# 3_IO_Module.net
KiCad netlist of a schematic drawn in Altium Designer
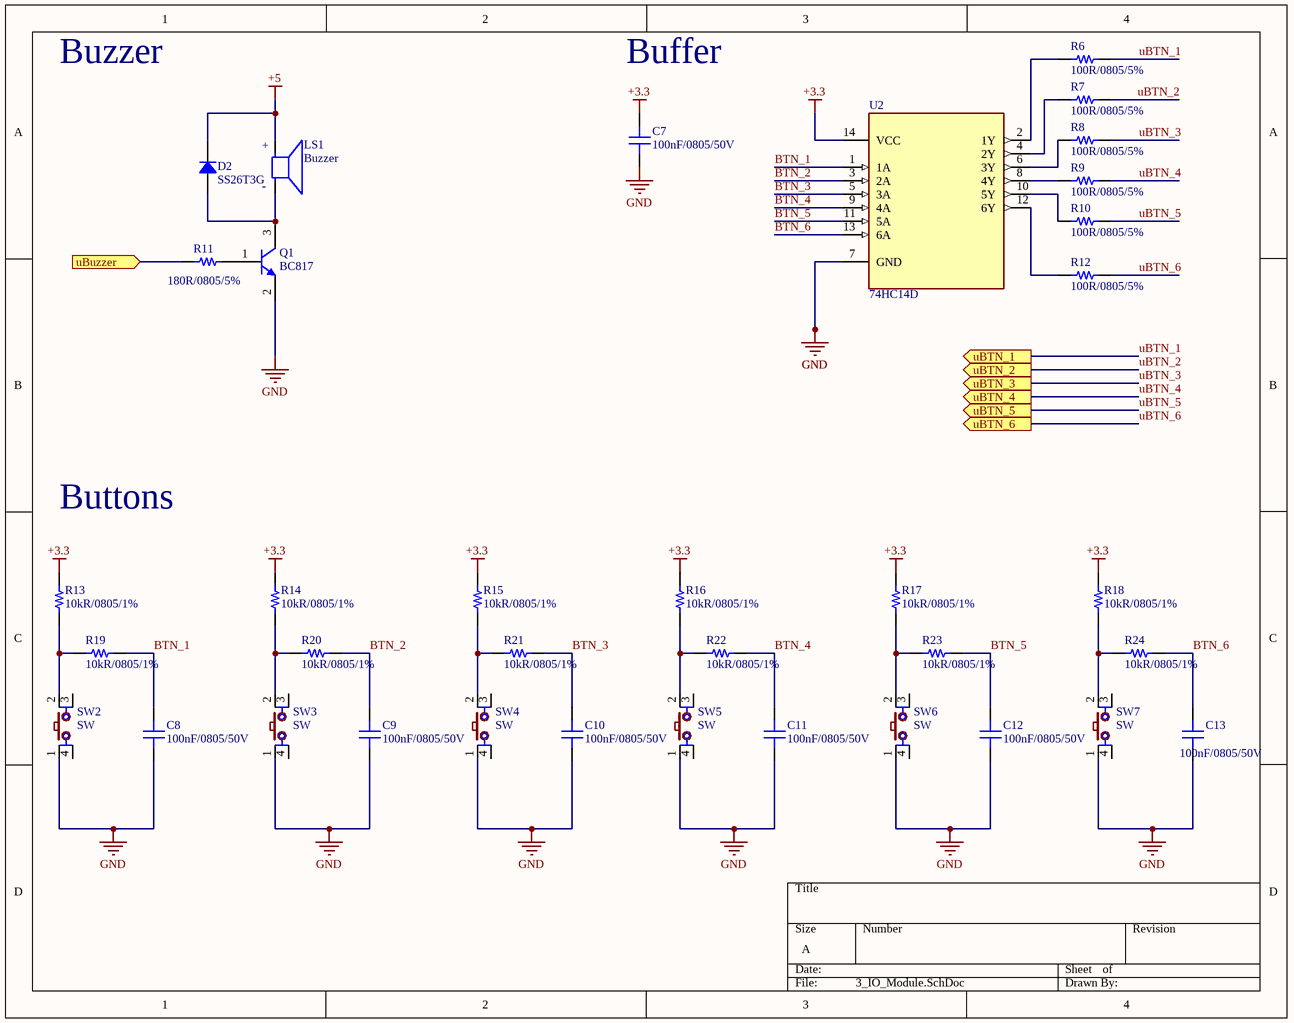
[diagram p0: 3_IO_Module.SchDoc]

(export (version "E")
  (design (tool "Eeschema 10.0.6"))
  (components
    (comp (ref "C7")
      (value "100nF/0805/50V")
      (footprint "CAP FILM 0805")
      (description "Multilayer Ceramic Capacitor, 0.1 uF, 50 V, ï¿½ 10%, X7R, 0805 [2012 Metric]")
      (fields
        (field (name "MANUFACTURER") "Samsung")
        (field (name "MANUFACTURER PART NUMBER") "CL21B104KBCNNNC")
      )
      (libsource (lib "NLOC_Altium_Library") (part "Capacitor - MLCC"))
    )
    (comp (ref "C8")
      (value "100nF/0805/50V")
      (footprint "CAP FILM 0805")
      (description "Multilayer Ceramic Capacitor, 0.1 uF, 50 V, ï¿½ 10%, X7R, 0805 [2012 Metric]")
      (fields
        (field (name "MANUFACTURER") "Samsung")
        (field (name "MANUFACTURER PART NUMBER") "CL21B104KBCNNNC")
      )
      (libsource (lib "NLOC_Altium_Library") (part "Capacitor - MLCC"))
    )
    (comp (ref "C9")
      (value "100nF/0805/50V")
      (footprint "CAP FILM 0805")
      (description "Multilayer Ceramic Capacitor, 0.1 uF, 50 V, ï¿½ 10%, X7R, 0805 [2012 Metric]")
      (fields
        (field (name "MANUFACTURER") "Samsung")
        (field (name "MANUFACTURER PART NUMBER") "CL21B104KBCNNNC")
      )
      (libsource (lib "NLOC_Altium_Library") (part "Capacitor - MLCC"))
    )
    (comp (ref "C10")
      (value "100nF/0805/50V")
      (footprint "CAP FILM 0805")
      (description "Multilayer Ceramic Capacitor, 0.1 uF, 50 V, ï¿½ 10%, X7R, 0805 [2012 Metric]")
      (fields
        (field (name "MANUFACTURER") "Samsung")
        (field (name "MANUFACTURER PART NUMBER") "CL21B104KBCNNNC")
      )
      (libsource (lib "NLOC_Altium_Library") (part "Capacitor - MLCC"))
    )
    (comp (ref "C11")
      (value "100nF/0805/50V")
      (footprint "CAP FILM 0805")
      (description "Multilayer Ceramic Capacitor, 0.1 uF, 50 V, ï¿½ 10%, X7R, 0805 [2012 Metric]")
      (fields
        (field (name "MANUFACTURER") "Samsung")
        (field (name "MANUFACTURER PART NUMBER") "CL21B104KBCNNNC")
      )
      (libsource (lib "NLOC_Altium_Library") (part "Capacitor - MLCC"))
    )
    (comp (ref "C12")
      (value "100nF/0805/50V")
      (footprint "CAP FILM 0805")
      (description "Multilayer Ceramic Capacitor, 0.1 uF, 50 V, ï¿½ 10%, X7R, 0805 [2012 Metric]")
      (fields
        (field (name "MANUFACTURER") "Samsung")
        (field (name "MANUFACTURER PART NUMBER") "CL21B104KBCNNNC")
      )
      (libsource (lib "NLOC_Altium_Library") (part "Capacitor - MLCC"))
    )
    (comp (ref "C13")
      (value "100nF/0805/50V")
      (footprint "CAP FILM 0805")
      (description "Multilayer Ceramic Capacitor, 0.1 uF, 50 V, ï¿½ 10%, X7R, 0805 [2012 Metric]")
      (fields
        (field (name "MANUFACTURER") "Samsung")
        (field (name "MANUFACTURER PART NUMBER") "CL21B104KBCNNNC")
      )
      (libsource (lib "NLOC_Altium_Library") (part "Capacitor - MLCC"))
    )
    (comp (ref "D2")
      (value "SS26T3G")
      (footprint "ST DO214AC SMA")
      (description "VR=60V IF=2A")
      (fields (field (name "MANUFACTURER") "ON Semiconductor"))
      (libsource (lib "NLOC_Altium_Library") (part "Diode"))
    )
    (comp (ref "LS1")
      (value "Buzzer")
      (footprint "XDCR_AT-1224-TWT-5V-2-R")
      (description "AUDIO TRANSDUCER 12 VP-P 85 DB 2400 HZ")
      (fields (field (name "MP") "AT-1224-TWT-5V-2-R"))
      (libsource (lib "AT-1224-TWT-5V-2-R") (part "AT-1224-TWT-5V-2-R"))
    )
    (comp (ref "Q1")
      (value "BC817")
      (footprint "TI SOT-23-3 DBZ")
      (libsource (lib "NLOC_Altium_Library") (part "BJT NPN"))
    )
    (comp (ref "R6")
      (value "100R/0805/5%")
      (footprint "RES 0805_2012")
      (description "SMD Chip Resistor, 100 Ohm, ± 5%, 125 mW, 0805 [2012 Metric], Thick Film, General Purpose")
      (fields
        (field (name "MANUFACTURER") "Yageo")
        (field (name "MANUFACTURER PART NUMBER") "AC0805JR-07100RL")
      )
      (libsource (lib "NLOC_Altium_Library") (part "Resistor"))
    )
    (comp (ref "R7")
      (value "100R/0805/5%")
      (footprint "RES 0805_2012")
      (description "SMD Chip Resistor, 100 Ohm, ± 5%, 125 mW, 0805 [2012 Metric], Thick Film, General Purpose")
      (fields
        (field (name "MANUFACTURER") "Yageo")
        (field (name "MANUFACTURER PART NUMBER") "AC0805JR-07100RL")
      )
      (libsource (lib "NLOC_Altium_Library") (part "Resistor"))
    )
    (comp (ref "R8")
      (value "100R/0805/5%")
      (footprint "RES 0805_2012")
      (description "SMD Chip Resistor, 100 Ohm, ± 5%, 125 mW, 0805 [2012 Metric], Thick Film, General Purpose")
      (fields
        (field (name "MANUFACTURER") "Yageo")
        (field (name "MANUFACTURER PART NUMBER") "AC0805JR-07100RL")
      )
      (libsource (lib "NLOC_Altium_Library") (part "Resistor"))
    )
    (comp (ref "R9")
      (value "100R/0805/5%")
      (footprint "RES 0805_2012")
      (description "SMD Chip Resistor, 100 Ohm, ± 5%, 125 mW, 0805 [2012 Metric], Thick Film, General Purpose")
      (fields
        (field (name "MANUFACTURER") "Yageo")
        (field (name "MANUFACTURER PART NUMBER") "AC0805JR-07100RL")
      )
      (libsource (lib "NLOC_Altium_Library") (part "Resistor"))
    )
    (comp (ref "R10")
      (value "100R/0805/5%")
      (footprint "RES 0805_2012")
      (description "SMD Chip Resistor, 100 Ohm, ± 5%, 125 mW, 0805 [2012 Metric], Thick Film, General Purpose")
      (fields
        (field (name "MANUFACTURER") "Yageo")
        (field (name "MANUFACTURER PART NUMBER") "AC0805JR-07100RL")
      )
      (libsource (lib "NLOC_Altium_Library") (part "Resistor"))
    )
    (comp (ref "R11")
      (value "180R/0805/5%")
      (footprint "RES 0805_2012")
      (description "Anti-Sulfurated Chip Resistor Thick Film 0805 180Ohm 1% Paper T/R")
      (fields
        (field (name "MANUFACTURER") "Yageo")
        (field (name "MANUFACTURER PART NUMBER") "AF0805FR-07180RL")
      )
      (libsource (lib "NLOC_Altium_Library") (part "Resistor"))
    )
    (comp (ref "R12")
      (value "100R/0805/5%")
      (footprint "RES 0805_2012")
      (description "SMD Chip Resistor, 100 Ohm, ± 5%, 125 mW, 0805 [2012 Metric], Thick Film, General Purpose")
      (fields
        (field (name "MANUFACTURER") "Yageo")
        (field (name "MANUFACTURER PART NUMBER") "AC0805JR-07100RL")
      )
      (libsource (lib "NLOC_Altium_Library") (part "Resistor"))
    )
    (comp (ref "R13")
      (value "10kR/0805/1%")
      (footprint "RES 0805_2012")
      (description "SMD Chip Resistor, 10 kOhm, ï¿½ 1%, 125 mW, 0805 [2012 Metric], Thick Film, General Purpose")
      (fields
        (field (name "MANUFACTURER") "Yageo")
        (field (name "MANUFACTURER PART NUMBER") "RC0805FR-0710KL")
      )
      (libsource (lib "NLOC_Altium_Library") (part "Resistor"))
    )
    (comp (ref "R14")
      (value "10kR/0805/1%")
      (footprint "RES 0805_2012")
      (description "SMD Chip Resistor, 10 kOhm, ï¿½ 1%, 125 mW, 0805 [2012 Metric], Thick Film, General Purpose")
      (fields
        (field (name "MANUFACTURER") "Yageo")
        (field (name "MANUFACTURER PART NUMBER") "RC0805FR-0710KL")
      )
      (libsource (lib "NLOC_Altium_Library") (part "Resistor"))
    )
    (comp (ref "R15")
      (value "10kR/0805/1%")
      (footprint "RES 0805_2012")
      (description "SMD Chip Resistor, 10 kOhm, ï¿½ 1%, 125 mW, 0805 [2012 Metric], Thick Film, General Purpose")
      (fields
        (field (name "MANUFACTURER") "Yageo")
        (field (name "MANUFACTURER PART NUMBER") "RC0805FR-0710KL")
      )
      (libsource (lib "NLOC_Altium_Library") (part "Resistor"))
    )
    (comp (ref "R16")
      (value "10kR/0805/1%")
      (footprint "RES 0805_2012")
      (description "SMD Chip Resistor, 10 kOhm, ï¿½ 1%, 125 mW, 0805 [2012 Metric], Thick Film, General Purpose")
      (fields
        (field (name "MANUFACTURER") "Yageo")
        (field (name "MANUFACTURER PART NUMBER") "RC0805FR-0710KL")
      )
      (libsource (lib "NLOC_Altium_Library") (part "Resistor"))
    )
    (comp (ref "R17")
      (value "10kR/0805/1%")
      (footprint "RES 0805_2012")
      (description "SMD Chip Resistor, 10 kOhm, ï¿½ 1%, 125 mW, 0805 [2012 Metric], Thick Film, General Purpose")
      (fields
        (field (name "MANUFACTURER") "Yageo")
        (field (name "MANUFACTURER PART NUMBER") "RC0805FR-0710KL")
      )
      (libsource (lib "NLOC_Altium_Library") (part "Resistor"))
    )
    (comp (ref "R18")
      (value "10kR/0805/1%")
      (footprint "RES 0805_2012")
      (description "SMD Chip Resistor, 10 kOhm, ï¿½ 1%, 125 mW, 0805 [2012 Metric], Thick Film, General Purpose")
      (fields
        (field (name "MANUFACTURER") "Yageo")
        (field (name "MANUFACTURER PART NUMBER") "RC0805FR-0710KL")
      )
      (libsource (lib "NLOC_Altium_Library") (part "Resistor"))
    )
    (comp (ref "R19")
      (value "10kR/0805/1%")
      (footprint "RES 0805_2012")
      (description "SMD Chip Resistor, 10 kOhm, ï¿½ 1%, 125 mW, 0805 [2012 Metric], Thick Film, General Purpose")
      (fields
        (field (name "MANUFACTURER") "Yageo")
        (field (name "MANUFACTURER PART NUMBER") "RC0805FR-0710KL")
      )
      (libsource (lib "NLOC_Altium_Library") (part "Resistor"))
    )
    (comp (ref "R20")
      (value "10kR/0805/1%")
      (footprint "RES 0805_2012")
      (description "SMD Chip Resistor, 10 kOhm, ï¿½ 1%, 125 mW, 0805 [2012 Metric], Thick Film, General Purpose")
      (fields
        (field (name "MANUFACTURER") "Yageo")
        (field (name "MANUFACTURER PART NUMBER") "RC0805FR-0710KL")
      )
      (libsource (lib "NLOC_Altium_Library") (part "Resistor"))
    )
    (comp (ref "R21")
      (value "10kR/0805/1%")
      (footprint "RES 0805_2012")
      (description "SMD Chip Resistor, 10 kOhm, ï¿½ 1%, 125 mW, 0805 [2012 Metric], Thick Film, General Purpose")
      (fields
        (field (name "MANUFACTURER") "Yageo")
        (field (name "MANUFACTURER PART NUMBER") "RC0805FR-0710KL")
      )
      (libsource (lib "NLOC_Altium_Library") (part "Resistor"))
    )
    (comp (ref "R22")
      (value "10kR/0805/1%")
      (footprint "RES 0805_2012")
      (description "SMD Chip Resistor, 10 kOhm, ï¿½ 1%, 125 mW, 0805 [2012 Metric], Thick Film, General Purpose")
      (fields
        (field (name "MANUFACTURER") "Yageo")
        (field (name "MANUFACTURER PART NUMBER") "RC0805FR-0710KL")
      )
      (libsource (lib "NLOC_Altium_Library") (part "Resistor"))
    )
    (comp (ref "R23")
      (value "10kR/0805/1%")
      (footprint "RES 0805_2012")
      (description "SMD Chip Resistor, 10 kOhm, ï¿½ 1%, 125 mW, 0805 [2012 Metric], Thick Film, General Purpose")
      (fields
        (field (name "MANUFACTURER") "Yageo")
        (field (name "MANUFACTURER PART NUMBER") "RC0805FR-0710KL")
      )
      (libsource (lib "NLOC_Altium_Library") (part "Resistor"))
    )
    (comp (ref "R24")
      (value "10kR/0805/1%")
      (footprint "RES 0805_2012")
      (description "SMD Chip Resistor, 10 kOhm, ï¿½ 1%, 125 mW, 0805 [2012 Metric], Thick Film, General Purpose")
      (fields
        (field (name "MANUFACTURER") "Yageo")
        (field (name "MANUFACTURER PART NUMBER") "RC0805FR-0710KL")
      )
      (libsource (lib "NLOC_Altium_Library") (part "Resistor"))
    )
    (comp (ref "SW2")
      (value "SW")
      (footprint "SW2-SMD")
      (description "Switch button 4 pin")
      (libsource (lib "LIBRARYALT") (part "SW4"))
    )
    (comp (ref "SW3")
      (value "SW")
      (footprint "SW2-SMD")
      (description "Switch button 4 pin")
      (libsource (lib "LIBRARYALT") (part "SW4"))
    )
    (comp (ref "SW4")
      (value "SW")
      (footprint "SW2-SMD")
      (description "Switch button 4 pin")
      (libsource (lib "LIBRARYALT") (part "SW4"))
    )
    (comp (ref "SW5")
      (value "SW")
      (footprint "SW2-SMD")
      (description "Switch button 4 pin")
      (libsource (lib "LIBRARYALT") (part "SW4"))
    )
    (comp (ref "SW6")
      (value "SW")
      (footprint "SW2-SMD")
      (description "Switch button 4 pin")
      (libsource (lib "LIBRARYALT") (part "SW4"))
    )
    (comp (ref "SW7")
      (value "SW")
      (footprint "SW2-SMD")
      (description "Switch button 4 pin")
      (libsource (lib "LIBRARYALT") (part "SW4"))
    )
    (comp (ref "U2")
      (value "74HC14D")
      (footprint "SOIC127P600X175-14N")
      (description "Inverter IC 6 Channel Schmitt Trigger 14-SOIC")
      (fields (field (name "MF") "Toshiba"))
      (libsource (lib "74HC14D") (part "74HC14D"))
    )
  )
  (nets
    (net (code "1") (name "+3.3") (class "Default")
      (node (ref "C7") (pin "2") (pinfunction "2_2") (pintype "passive"))
      (node (ref "R13") (pin "2") (pinfunction "2_2") (pintype "passive"))
      (node (ref "R14") (pin "2") (pinfunction "2_2") (pintype "passive"))
      (node (ref "R15") (pin "2") (pinfunction "2_2") (pintype "passive"))
      (node (ref "R16") (pin "2") (pinfunction "2_2") (pintype "passive"))
      (node (ref "R17") (pin "2") (pinfunction "2_2") (pintype "passive"))
      (node (ref "R18") (pin "2") (pinfunction "2_2") (pintype "passive"))
      (node (ref "U2") (pin "14") (pinfunction "VCC_14") (pintype "power_in"))
    )
    (net (code "2") (name "+5") (class "Default")
      (node (ref "D2") (pin "2") (pinfunction "2_2") (pintype "passive"))
      (node (ref "LS1") (pin "P") (pinfunction "P_P") (pintype "passive"))
    )
    (net (code "3") (name "/BTN_1") (class "Default")
      (node (ref "C8") (pin "2") (pinfunction "2_2") (pintype "passive"))
      (node (ref "R19") (pin "1") (pinfunction "1_1") (pintype "passive"))
      (node (ref "U2") (pin "1") (pinfunction "1A_1") (pintype "input"))
    )
    (net (code "4") (name "/BTN_2") (class "Default")
      (node (ref "C9") (pin "2") (pinfunction "2_2") (pintype "passive"))
      (node (ref "R20") (pin "1") (pinfunction "1_1") (pintype "passive"))
      (node (ref "U2") (pin "3") (pinfunction "2A_3") (pintype "input"))
    )
    (net (code "5") (name "/BTN_3") (class "Default")
      (node (ref "C10") (pin "2") (pinfunction "2_2") (pintype "passive"))
      (node (ref "R21") (pin "1") (pinfunction "1_1") (pintype "passive"))
      (node (ref "U2") (pin "5") (pinfunction "3A_5") (pintype "input"))
    )
    (net (code "6") (name "/BTN_4") (class "Default")
      (node (ref "C11") (pin "2") (pinfunction "2_2") (pintype "passive"))
      (node (ref "R22") (pin "1") (pinfunction "1_1") (pintype "passive"))
      (node (ref "U2") (pin "9") (pinfunction "4A_9") (pintype "input"))
    )
    (net (code "7") (name "/BTN_5") (class "Default")
      (node (ref "C12") (pin "2") (pinfunction "2_2") (pintype "passive"))
      (node (ref "R23") (pin "1") (pinfunction "1_1") (pintype "passive"))
      (node (ref "U2") (pin "11") (pinfunction "5A_11") (pintype "input"))
    )
    (net (code "8") (name "/BTN_6") (class "Default")
      (node (ref "C13") (pin "2") (pinfunction "2_2") (pintype "passive"))
      (node (ref "R24") (pin "1") (pinfunction "1_1") (pintype "passive"))
      (node (ref "U2") (pin "13") (pinfunction "6A_13") (pintype "input"))
    )
    (net (code "9") (name "/uBTN_1") (class "Default")
      (node (ref "R6") (pin "2") (pinfunction "2_2") (pintype "passive"))
    )
    (net (code "10") (name "/uBTN_2") (class "Default")
      (node (ref "R7") (pin "2") (pinfunction "2_2") (pintype "passive"))
    )
    (net (code "11") (name "/uBTN_3") (class "Default")
      (node (ref "R8") (pin "2") (pinfunction "2_2") (pintype "passive"))
    )
    (net (code "12") (name "/uBTN_4") (class "Default")
      (node (ref "R9") (pin "2") (pinfunction "2_2") (pintype "passive"))
    )
    (net (code "13") (name "/uBTN_5") (class "Default")
      (node (ref "R10") (pin "2") (pinfunction "2_2") (pintype "passive"))
    )
    (net (code "14") (name "/uBTN_6") (class "Default")
      (node (ref "R12") (pin "2") (pinfunction "2_2") (pintype "passive"))
    )
    (net (code "15") (name "/uBuzzer") (class "Default")
      (node (ref "R11") (pin "2") (pinfunction "2_2") (pintype "passive"))
    )
    (net (code "16") (name "GND") (class "Default")
      (node (ref "C10") (pin "1") (pinfunction "1_1") (pintype "passive"))
      (node (ref "C11") (pin "1") (pinfunction "1_1") (pintype "passive"))
      (node (ref "C12") (pin "1") (pinfunction "1_1") (pintype "passive"))
      (node (ref "C13") (pin "1") (pinfunction "1_1") (pintype "passive"))
      (node (ref "C7") (pin "1") (pinfunction "1_1") (pintype "passive"))
      (node (ref "C8") (pin "1") (pinfunction "1_1") (pintype "passive"))
      (node (ref "C9") (pin "1") (pinfunction "1_1") (pintype "passive"))
      (node (ref "Q1") (pin "2") (pinfunction "E_2") (pintype "passive"))
      (node (ref "SW2") (pin "1") (pintype "passive"))
      (node (ref "SW3") (pin "1") (pintype "passive"))
      (node (ref "SW4") (pin "1") (pintype "passive"))
      (node (ref "SW5") (pin "1") (pintype "passive"))
      (node (ref "SW6") (pin "1") (pintype "passive"))
      (node (ref "SW7") (pin "1") (pintype "passive"))
      (node (ref "U2") (pin "7") (pinfunction "GND_7") (pintype "passive"))
    )
    (net (code "17") (name "Net-(Q1-B)") (class "Default")
      (node (ref "Q1") (pin "1") (pinfunction "B_1") (pintype "passive"))
      (node (ref "R11") (pin "1") (pinfunction "1_1") (pintype "passive"))
    )
    (net (code "18") (name "Net-(Q1-C)") (class "Default")
      (node (ref "D2") (pin "1") (pinfunction "1_1") (pintype "passive"))
      (node (ref "LS1") (pin "N") (pinfunction "N_N") (pintype "passive"))
      (node (ref "Q1") (pin "3") (pinfunction "C_3") (pintype "passive"))
    )
    (net (code "19") (name "Net-(R13-Pad1)") (class "Default")
      (node (ref "R13") (pin "1") (pinfunction "1_1") (pintype "passive"))
      (node (ref "R19") (pin "2") (pinfunction "2_2") (pintype "passive"))
      (node (ref "SW2") (pin "2") (pinfunction "2_2") (pintype "passive"))
    )
    (net (code "20") (name "Net-(R14-Pad1)") (class "Default")
      (node (ref "R14") (pin "1") (pinfunction "1_1") (pintype "passive"))
      (node (ref "R20") (pin "2") (pinfunction "2_2") (pintype "passive"))
      (node (ref "SW3") (pin "2") (pinfunction "2_2") (pintype "passive"))
    )
    (net (code "21") (name "Net-(R15-Pad1)") (class "Default")
      (node (ref "R15") (pin "1") (pinfunction "1_1") (pintype "passive"))
      (node (ref "R21") (pin "2") (pinfunction "2_2") (pintype "passive"))
      (node (ref "SW4") (pin "2") (pinfunction "2_2") (pintype "passive"))
    )
    (net (code "22") (name "Net-(R16-Pad1)") (class "Default")
      (node (ref "R16") (pin "1") (pinfunction "1_1") (pintype "passive"))
      (node (ref "R22") (pin "2") (pinfunction "2_2") (pintype "passive"))
      (node (ref "SW5") (pin "2") (pinfunction "2_2") (pintype "passive"))
    )
    (net (code "23") (name "Net-(R17-Pad1)") (class "Default")
      (node (ref "R17") (pin "1") (pinfunction "1_1") (pintype "passive"))
      (node (ref "R23") (pin "2") (pinfunction "2_2") (pintype "passive"))
      (node (ref "SW6") (pin "2") (pinfunction "2_2") (pintype "passive"))
    )
    (net (code "24") (name "Net-(R18-Pad1)") (class "Default")
      (node (ref "R18") (pin "1") (pinfunction "1_1") (pintype "passive"))
      (node (ref "R24") (pin "2") (pinfunction "2_2") (pintype "passive"))
      (node (ref "SW7") (pin "2") (pinfunction "2_2") (pintype "passive"))
    )
    (net (code "25") (name "Net-(U2-1Y)") (class "Default")
      (node (ref "R6") (pin "1") (pinfunction "1_1") (pintype "passive"))
      (node (ref "U2") (pin "2") (pinfunction "1Y_2") (pintype "output"))
    )
    (net (code "26") (name "Net-(U2-2Y)") (class "Default")
      (node (ref "R7") (pin "1") (pinfunction "1_1") (pintype "passive"))
      (node (ref "U2") (pin "4") (pinfunction "2Y_4") (pintype "output"))
    )
    (net (code "27") (name "Net-(U2-3Y)") (class "Default")
      (node (ref "R8") (pin "1") (pinfunction "1_1") (pintype "passive"))
      (node (ref "U2") (pin "6") (pinfunction "3Y_6") (pintype "output"))
    )
    (net (code "28") (name "Net-(U2-4Y)") (class "Default")
      (node (ref "R9") (pin "1") (pinfunction "1_1") (pintype "passive"))
      (node (ref "U2") (pin "8") (pinfunction "4Y_8") (pintype "output"))
    )
    (net (code "29") (name "Net-(U2-5Y)") (class "Default")
      (node (ref "R10") (pin "1") (pinfunction "1_1") (pintype "passive"))
      (node (ref "U2") (pin "10") (pinfunction "5Y_10") (pintype "output"))
    )
    (net (code "30") (name "Net-(U2-6Y)") (class "Default")
      (node (ref "R12") (pin "1") (pinfunction "1_1") (pintype "passive"))
      (node (ref "U2") (pin "12") (pinfunction "6Y_12") (pintype "output"))
    )
    (net (code "31") (name "unconnected-(SW2-Pad3)") (class "Default")
      (node (ref "SW2") (pin "3") (pinfunction "3_3") (pintype "passive"))
    )
    (net (code "32") (name "unconnected-(SW2-Pad4)") (class "Default")
      (node (ref "SW2") (pin "4") (pinfunction "4_4") (pintype "passive"))
    )
    (net (code "33") (name "unconnected-(SW3-Pad3)") (class "Default")
      (node (ref "SW3") (pin "3") (pinfunction "3_3") (pintype "passive"))
    )
    (net (code "34") (name "unconnected-(SW3-Pad4)") (class "Default")
      (node (ref "SW3") (pin "4") (pinfunction "4_4") (pintype "passive"))
    )
    (net (code "35") (name "unconnected-(SW4-Pad3)") (class "Default")
      (node (ref "SW4") (pin "3") (pinfunction "3_3") (pintype "passive"))
    )
    (net (code "36") (name "unconnected-(SW4-Pad4)") (class "Default")
      (node (ref "SW4") (pin "4") (pinfunction "4_4") (pintype "passive"))
    )
    (net (code "37") (name "unconnected-(SW5-Pad3)") (class "Default")
      (node (ref "SW5") (pin "3") (pinfunction "3_3") (pintype "passive"))
    )
    (net (code "38") (name "unconnected-(SW5-Pad4)") (class "Default")
      (node (ref "SW5") (pin "4") (pinfunction "4_4") (pintype "passive"))
    )
    (net (code "39") (name "unconnected-(SW6-Pad3)") (class "Default")
      (node (ref "SW6") (pin "3") (pinfunction "3_3") (pintype "passive"))
    )
    (net (code "40") (name "unconnected-(SW6-Pad4)") (class "Default")
      (node (ref "SW6") (pin "4") (pinfunction "4_4") (pintype "passive"))
    )
    (net (code "41") (name "unconnected-(SW7-Pad3)") (class "Default")
      (node (ref "SW7") (pin "3") (pinfunction "3_3") (pintype "passive"))
    )
    (net (code "42") (name "unconnected-(SW7-Pad4)") (class "Default")
      (node (ref "SW7") (pin "4") (pinfunction "4_4") (pintype "passive"))
    )
  )
)
